# mymote-core.net
KiCad netlist of a schematic drawn in EAGLE
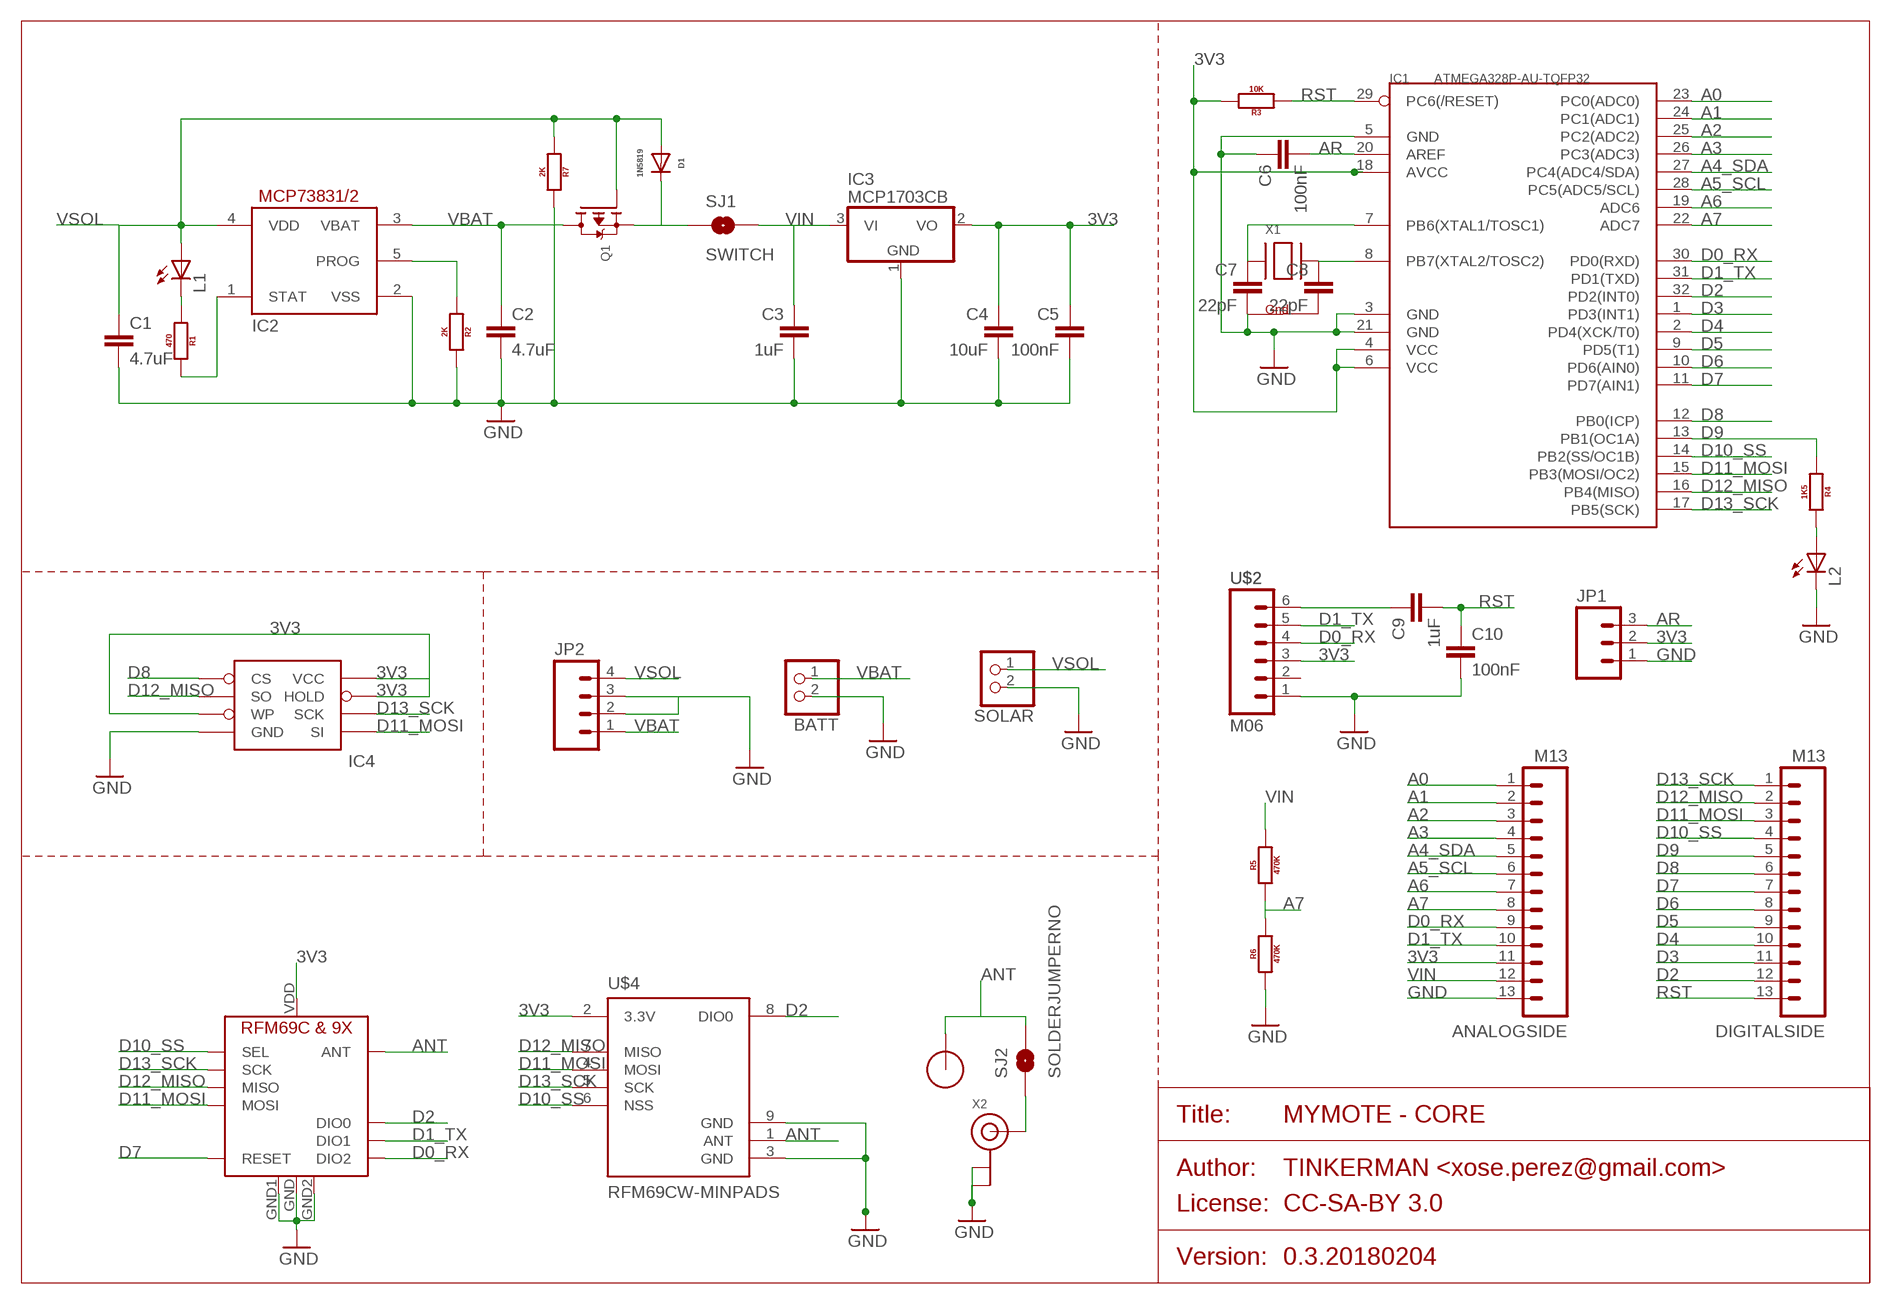
[diagram p0: schematic, sheet 1]

(export (version "E")
  (design (tool "Eeschema 10.0.6"))
  (components
    (comp (ref "ANALOGSIDE")
      (value "M13")
      (footprint "eagle-import:1X13_NO_SILK")
      (libsource (lib "eagle-import") (part "M13"))
    )
    (comp (ref "BATT")
      (value "JST_2PIN-SMT-RA")
      (footprint "eagle-import:JST-PH-2-SMT-RA")
      (libsource (lib "eagle-import") (part "JST_2PIN-SMT-RA"))
    )
    (comp (ref "C1")
      (value "4.7uF")
      (footprint "eagle-import:0805")
      (libsource (lib "eagle-import") (part "C-EU0805"))
    )
    (comp (ref "C2")
      (value "4.7uF")
      (footprint "eagle-import:0805")
      (libsource (lib "eagle-import") (part "C-EU0805"))
    )
    (comp (ref "C3")
      (value "1uF")
      (footprint "eagle-import:0805")
      (libsource (lib "eagle-import") (part "C-EU0805"))
    )
    (comp (ref "C4")
      (value "10uF")
      (footprint "eagle-import:0805")
      (libsource (lib "eagle-import") (part "C-EU0805"))
    )
    (comp (ref "C5")
      (value "100nF")
      (footprint "eagle-import:0805")
      (libsource (lib "eagle-import") (part "C-EU0805"))
    )
    (comp (ref "C6")
      (value "100nF")
      (footprint "eagle-import:0805")
      (libsource (lib "eagle-import") (part "C-EU0805"))
    )
    (comp (ref "C7")
      (value "22pF")
      (footprint "eagle-import:0805")
      (libsource (lib "eagle-import") (part "C-EU0805"))
    )
    (comp (ref "C8")
      (value "22pF")
      (footprint "eagle-import:0805")
      (libsource (lib "eagle-import") (part "C-EU0805"))
    )
    (comp (ref "C9")
      (value "1uF")
      (footprint "eagle-import:0805")
      (libsource (lib "eagle-import") (part "C-EU0805"))
    )
    (comp (ref "C10")
      (value "100nF")
      (footprint "eagle-import:0805")
      (libsource (lib "eagle-import") (part "C-EU0805"))
    )
    (comp (ref "D1")
      (value "1N5819")
      (footprint "eagle-import:0805_DIODE")
      (libsource (lib "eagle-import") (part "DIODE-SMD"))
    )
    (comp (ref "DIGITALSIDE")
      (value "M13")
      (footprint "eagle-import:1X13_NO_SILK")
      (libsource (lib "eagle-import") (part "M13"))
    )
    (comp (ref "IC1")
      (value "ATMEGA328P-AU-TQFP32")
      (footprint "eagle-import:TQFP32-0.8-7X7MM")
      (fields (field (name "MPN") "ATMEGA328P-AU"))
      (libsource (lib "eagle-import") (part "MCU-ATMEGA328P-AU(TQFP32)"))
    )
    (comp (ref "IC2")
      (value "MCP73831/OT")
      (footprint "eagle-import:SOT23-5L")
      (libsource (lib "eagle-import") (part "MCP73831/OT"))
    )
    (comp (ref "IC3")
      (value "MCP1703CB")
      (footprint "eagle-import:SOT23")
      (libsource (lib "eagle-import") (part "MCP1703CB"))
    )
    (comp (ref "IC4")
      (value "AT25F512BWIDE_5.3MM")
      (footprint "eagle-import:SO08WIDE")
      (libsource (lib "eagle-import") (part "AT25F512BWIDE_5.3MM"))
    )
    (comp (ref "JP1")
      (value "M03PTH")
      (footprint "eagle-import:1X03")
      (libsource (lib "eagle-import") (part "M03PTH"))
    )
    (comp (ref "JP2")
      (value "M04PTH")
      (footprint "eagle-import:1X04")
      (libsource (lib "eagle-import") (part "M04PTH"))
    )
    (comp (ref "L1")
      (value "LED_0805")
      (footprint "eagle-import:0805_DIODE")
      (libsource (lib "eagle-import") (part "LED_0805"))
    )
    (comp (ref "L2")
      (value "LED_0805")
      (footprint "eagle-import:0805_DIODE")
      (libsource (lib "eagle-import") (part "LED_0805"))
    )
    (comp (ref "Q1")
      (value "MOSFET-PWIDE")
      (footprint "eagle-import:SOT23-WIDE")
      (libsource (lib "eagle-import") (part "MOSFET-PWIDE"))
    )
    (comp (ref "R1")
      (value "470")
      (footprint "eagle-import:0805")
      (libsource (lib "eagle-import") (part "RESISTOR0805"))
    )
    (comp (ref "R2")
      (value "2K")
      (footprint "eagle-import:0805")
      (libsource (lib "eagle-import") (part "RESISTOR0805"))
    )
    (comp (ref "R3")
      (value "10K")
      (footprint "eagle-import:0805")
      (libsource (lib "eagle-import") (part "RESISTOR0805"))
    )
    (comp (ref "R4")
      (value "1K5")
      (footprint "eagle-import:0805")
      (libsource (lib "eagle-import") (part "RESISTOR0805"))
    )
    (comp (ref "R5")
      (value "470K")
      (footprint "eagle-import:0805")
      (libsource (lib "eagle-import") (part "RESISTOR0805"))
    )
    (comp (ref "R6")
      (value "470K")
      (footprint "eagle-import:0805")
      (libsource (lib "eagle-import") (part "RESISTOR0805"))
    )
    (comp (ref "R7")
      (value "2K")
      (footprint "eagle-import:0805")
      (libsource (lib "eagle-import") (part "RESISTOR0805"))
    )
    (comp (ref "SJ1")
      (value "SWITCH")
      (footprint "eagle-import:SJ_2S-TRACE-PTH")
      (libsource (lib "eagle-import") (part "SOLDERJUMPERTRACE-PTH"))
    )
    (comp (ref "SJ2")
      (value "SOLDERJUMPERNO")
      (footprint "eagle-import:SJ_2S-NO")
      (libsource (lib "eagle-import") (part "SOLDERJUMPERNO"))
    )
    (comp (ref "SOLAR")
      (value "JST_2PIN-SMT-RA")
      (footprint "eagle-import:JST-PH-2-SMT-RA")
      (libsource (lib "eagle-import") (part "JST_2PIN-SMT-RA"))
    )
    (comp (ref "U$1")
      (value "RFM12B_ANTENNA")
      (footprint "eagle-import:RFM12B-ANTENNA")
      (libsource (lib "eagle-import") (part "RFM12B_ANTENNA"))
    )
    (comp (ref "U$2")
      (value "M06")
      (footprint "eagle-import:1X06_NO_SILK")
      (libsource (lib "eagle-import") (part "M06"))
    )
    (comp (ref "U$3")
      (value "RFM69HCW-RFM95")
      (footprint "eagle-import:RFM69HCW-RFM95-MINPADS")
      (libsource (lib "eagle-import") (part "RFM69HCW-RFM95"))
    )
    (comp (ref "U$4")
      (value "RFM69CW-MINPADS")
      (footprint "eagle-import:RFM69CW-MINPADS")
      (libsource (lib "eagle-import") (part "RFM69CW-MINPADS"))
    )
    (comp (ref "X1")
      (value "XTAL-4-3225")
      (footprint "eagle-import:NX3225")
      (libsource (lib "eagle-import") (part "XTAL-4-3225"))
    )
    (comp (ref "X2")
      (value "ANTENNA_U.FL")
      (footprint "eagle-import:U.FL")
      (libsource (lib "eagle-import") (part "ANTENNA_U.FL"))
    )
  )
  (nets
    (net (code "1") (name "/3V3") (class "Default")
      (node (ref "ANALOGSIDE") (pin "11") (pinfunction "11_11") (pintype "passive"))
      (node (ref "C4") (pin "1") (pinfunction "1_1") (pintype "passive"))
      (node (ref "C5") (pin "1") (pinfunction "1_1") (pintype "passive"))
      (node (ref "IC1") (pin "18") (pinfunction "AVCC_18") (pintype "bidirectional"))
      (node (ref "IC1") (pin "4") (pinfunction "VCC_4") (pintype "bidirectional"))
      (node (ref "IC1") (pin "6") (pinfunction "VCC_6") (pintype "bidirectional"))
      (node (ref "IC3") (pin "2") (pinfunction "VO_2") (pintype "passive"))
      (node (ref "IC4") (pin "3") (pinfunction "WP_3") (pintype "bidirectional"))
      (node (ref "IC4") (pin "7") (pinfunction "HOLD_7") (pintype "bidirectional"))
      (node (ref "IC4") (pin "8") (pinfunction "VCC_8") (pintype "bidirectional"))
      (node (ref "JP1") (pin "2") (pinfunction "2_2") (pintype "passive"))
      (node (ref "R3") (pin "2") (pinfunction "2_2") (pintype "passive"))
      (node (ref "U$2") (pin "3") (pinfunction "3_3") (pintype "passive"))
      (node (ref "U$3") (pin "VDD") (pinfunction "VCC_VDD") (pintype "power_in"))
      (node (ref "U$4") (pin "2") (pinfunction "3.3V_2") (pintype "power_in"))
    )
    (net (code "2") (name "/A0") (class "Default")
      (node (ref "ANALOGSIDE") (pin "1") (pinfunction "1_1") (pintype "passive"))
      (node (ref "IC1") (pin "23") (pinfunction "PC0(ADC0)_23") (pintype "bidirectional"))
    )
    (net (code "3") (name "/A1") (class "Default")
      (node (ref "ANALOGSIDE") (pin "2") (pinfunction "2_2") (pintype "passive"))
      (node (ref "IC1") (pin "24") (pinfunction "PC1(ADC1)_24") (pintype "bidirectional"))
    )
    (net (code "4") (name "/A2") (class "Default")
      (node (ref "ANALOGSIDE") (pin "3") (pinfunction "3_3") (pintype "passive"))
      (node (ref "IC1") (pin "25") (pinfunction "PC2(ADC2)_25") (pintype "bidirectional"))
    )
    (net (code "5") (name "/A3") (class "Default")
      (node (ref "ANALOGSIDE") (pin "4") (pinfunction "4_4") (pintype "passive"))
      (node (ref "IC1") (pin "26") (pinfunction "PC3(ADC3)_26") (pintype "bidirectional"))
    )
    (net (code "6") (name "/A4_SDA") (class "Default")
      (node (ref "ANALOGSIDE") (pin "5") (pinfunction "5_5") (pintype "passive"))
      (node (ref "IC1") (pin "27") (pinfunction "PC4(ADC4/SDA)_27") (pintype "bidirectional"))
    )
    (net (code "7") (name "/A5_SCL") (class "Default")
      (node (ref "ANALOGSIDE") (pin "6") (pinfunction "6_6") (pintype "passive"))
      (node (ref "IC1") (pin "28") (pinfunction "PC5(ADC5/SCL)_28") (pintype "bidirectional"))
    )
    (net (code "8") (name "/A6") (class "Default")
      (node (ref "ANALOGSIDE") (pin "7") (pinfunction "7_7") (pintype "passive"))
      (node (ref "IC1") (pin "19") (pinfunction "ADC6_19") (pintype "bidirectional"))
    )
    (net (code "9") (name "/A7") (class "Default")
      (node (ref "ANALOGSIDE") (pin "8") (pinfunction "8_8") (pintype "passive"))
      (node (ref "IC1") (pin "22") (pinfunction "ADC7_22") (pintype "bidirectional"))
      (node (ref "R5") (pin "1") (pinfunction "1_1") (pintype "passive"))
      (node (ref "R6") (pin "2") (pinfunction "2_2") (pintype "passive"))
    )
    (net (code "10") (name "/ANT") (class "Default")
      (node (ref "SJ2") (pin "2") (pinfunction "2_2") (pintype "passive"))
      (node (ref "U$1") (pin "P$1") (pinfunction "1_P$1") (pintype "bidirectional"))
      (node (ref "U$3") (pin "ANT") (pinfunction "ANT_ANT") (pintype "passive"))
      (node (ref "U$4") (pin "1") (pinfunction "ANT_1") (pintype "passive"))
    )
    (net (code "11") (name "/AR") (class "Default")
      (node (ref "C6") (pin "2") (pinfunction "2_2") (pintype "passive"))
      (node (ref "IC1") (pin "20") (pinfunction "AREF_20") (pintype "bidirectional"))
      (node (ref "JP1") (pin "3") (pinfunction "3_3") (pintype "passive"))
    )
    (net (code "12") (name "/D0_RX") (class "Default")
      (node (ref "ANALOGSIDE") (pin "9") (pinfunction "9_9") (pintype "passive"))
      (node (ref "IC1") (pin "30") (pinfunction "PD0(RXD)_30") (pintype "bidirectional"))
      (node (ref "U$2") (pin "4") (pinfunction "4_4") (pintype "passive"))
      (node (ref "U$3") (pin "DIO2") (pinfunction "DIO2_DIO2") (pintype "bidirectional"))
    )
    (net (code "13") (name "/D1_TX") (class "Default")
      (node (ref "ANALOGSIDE") (pin "10") (pinfunction "10_10") (pintype "passive"))
      (node (ref "IC1") (pin "31") (pinfunction "PD1(TXD)_31") (pintype "bidirectional"))
      (node (ref "U$2") (pin "5") (pinfunction "5_5") (pintype "passive"))
      (node (ref "U$3") (pin "DIO1") (pinfunction "DIO1_DIO1") (pintype "bidirectional"))
    )
    (net (code "14") (name "/D2") (class "Default")
      (node (ref "DIGITALSIDE") (pin "12") (pinfunction "12_12") (pintype "passive"))
      (node (ref "IC1") (pin "32") (pinfunction "PD2(INT0)_32") (pintype "bidirectional"))
      (node (ref "U$3") (pin "DIO0") (pinfunction "DIO0_DIO0") (pintype "bidirectional"))
      (node (ref "U$4") (pin "8") (pinfunction "DIO0_8") (pintype "bidirectional"))
    )
    (net (code "15") (name "/D3") (class "Default")
      (node (ref "DIGITALSIDE") (pin "11") (pinfunction "11_11") (pintype "passive"))
      (node (ref "IC1") (pin "1") (pinfunction "PD3(INT1)_1") (pintype "bidirectional"))
    )
    (net (code "16") (name "/D4") (class "Default")
      (node (ref "DIGITALSIDE") (pin "10") (pinfunction "10_10") (pintype "passive"))
      (node (ref "IC1") (pin "2") (pinfunction "PD4(XCK/T0)_2") (pintype "bidirectional"))
    )
    (net (code "17") (name "/D5") (class "Default")
      (node (ref "DIGITALSIDE") (pin "9") (pinfunction "9_9") (pintype "passive"))
      (node (ref "IC1") (pin "9") (pinfunction "PD5(T1)_9") (pintype "bidirectional"))
    )
    (net (code "18") (name "/D6") (class "Default")
      (node (ref "DIGITALSIDE") (pin "8") (pinfunction "8_8") (pintype "passive"))
      (node (ref "IC1") (pin "10") (pinfunction "PD6(AIN0)_10") (pintype "bidirectional"))
    )
    (net (code "19") (name "/D7") (class "Default")
      (node (ref "DIGITALSIDE") (pin "7") (pinfunction "7_7") (pintype "passive"))
      (node (ref "IC1") (pin "11") (pinfunction "PD7(AIN1)_11") (pintype "bidirectional"))
      (node (ref "U$3") (pin "RESET") (pinfunction "RESET_RESET") (pintype "input"))
    )
    (net (code "20") (name "/D8") (class "Default")
      (node (ref "DIGITALSIDE") (pin "6") (pinfunction "6_6") (pintype "passive"))
      (node (ref "IC1") (pin "12") (pinfunction "PB0(ICP)_12") (pintype "bidirectional"))
      (node (ref "IC4") (pin "1") (pinfunction "CS_1") (pintype "bidirectional"))
    )
    (net (code "21") (name "/D9") (class "Default")
      (node (ref "DIGITALSIDE") (pin "5") (pinfunction "5_5") (pintype "passive"))
      (node (ref "IC1") (pin "13") (pinfunction "PB1(OC1A)_13") (pintype "bidirectional"))
      (node (ref "R4") (pin "1") (pinfunction "1_1") (pintype "passive"))
    )
    (net (code "22") (name "/D10_SS") (class "Default")
      (node (ref "DIGITALSIDE") (pin "4") (pinfunction "4_4") (pintype "passive"))
      (node (ref "IC1") (pin "14") (pinfunction "PB2(SS/OC1B)_14") (pintype "bidirectional"))
      (node (ref "U$3") (pin "NSS") (pinfunction "SEL_NSS") (pintype "input"))
      (node (ref "U$4") (pin "6") (pinfunction "NSS_6") (pintype "input"))
    )
    (net (code "23") (name "/D11_MOSI") (class "Default")
      (node (ref "DIGITALSIDE") (pin "3") (pinfunction "3_3") (pintype "passive"))
      (node (ref "IC1") (pin "15") (pinfunction "PB3(MOSI/OC2)_15") (pintype "bidirectional"))
      (node (ref "IC4") (pin "5") (pinfunction "SI_5") (pintype "bidirectional"))
      (node (ref "U$3") (pin "MOSI") (pinfunction "MOSI_MOSI") (pintype "input"))
      (node (ref "U$4") (pin "4") (pinfunction "MOSI_4") (pintype "input"))
    )
    (net (code "24") (name "/D12_MISO") (class "Default")
      (node (ref "DIGITALSIDE") (pin "2") (pinfunction "2_2") (pintype "passive"))
      (node (ref "IC1") (pin "16") (pinfunction "PB4(MISO)_16") (pintype "bidirectional"))
      (node (ref "IC4") (pin "2") (pinfunction "SO_2") (pintype "bidirectional"))
      (node (ref "U$3") (pin "MISO") (pinfunction "MISO_MISO") (pintype "output"))
      (node (ref "U$4") (pin "7") (pinfunction "MISO_7") (pintype "bidirectional"))
    )
    (net (code "25") (name "/D13_SCK") (class "Default")
      (node (ref "DIGITALSIDE") (pin "1") (pinfunction "1_1") (pintype "passive"))
      (node (ref "IC1") (pin "17") (pinfunction "PB5(SCK)_17") (pintype "bidirectional"))
      (node (ref "IC4") (pin "6") (pinfunction "SCK_6") (pintype "bidirectional"))
      (node (ref "U$3") (pin "SCK") (pinfunction "SCK_SCK") (pintype "input"))
      (node (ref "U$4") (pin "5") (pinfunction "SCK_5") (pintype "input"))
    )
    (net (code "26") (name "/RST") (class "Default")
      (node (ref "C10") (pin "1") (pinfunction "1_1") (pintype "passive"))
      (node (ref "C9") (pin "2") (pinfunction "2_2") (pintype "passive"))
      (node (ref "DIGITALSIDE") (pin "13") (pinfunction "13_13") (pintype "passive"))
      (node (ref "IC1") (pin "29") (pinfunction "PC6(/RESET)_29") (pintype "bidirectional"))
      (node (ref "R3") (pin "1") (pinfunction "1_1") (pintype "passive"))
    )
    (net (code "27") (name "/VBAT") (class "Default")
      (node (ref "BATT") (pin "1") (pinfunction "2_1") (pintype "passive"))
      (node (ref "C2") (pin "1") (pinfunction "1_1") (pintype "passive"))
      (node (ref "IC2") (pin "3") (pinfunction "VBAT_3") (pintype "bidirectional"))
      (node (ref "JP2") (pin "1") (pinfunction "1_1") (pintype "passive"))
      (node (ref "Q1") (pin "3") (pinfunction "D_3") (pintype "passive"))
    )
    (net (code "28") (name "/VIN") (class "Default")
      (node (ref "ANALOGSIDE") (pin "12") (pinfunction "12_12") (pintype "passive"))
      (node (ref "C3") (pin "1") (pinfunction "1_1") (pintype "passive"))
      (node (ref "IC3") (pin "3") (pinfunction "VI_3") (pintype "input"))
      (node (ref "R5") (pin "2") (pinfunction "2_2") (pintype "passive"))
      (node (ref "SJ1") (pin "2") (pinfunction "2_2") (pintype "passive"))
    )
    (net (code "29") (name "/VSOL") (class "Default")
      (node (ref "C1") (pin "1") (pinfunction "1_1") (pintype "passive"))
      (node (ref "D1") (pin "A") (pinfunction "A_A") (pintype "passive"))
      (node (ref "IC2") (pin "4") (pinfunction "VDD_4") (pintype "power_in"))
      (node (ref "JP2") (pin "4") (pinfunction "4_4") (pintype "passive"))
      (node (ref "L1") (pin "A") (pinfunction "A_A") (pintype "passive"))
      (node (ref "Q1") (pin "1") (pinfunction "G_1") (pintype "passive"))
      (node (ref "R7") (pin "1") (pinfunction "1_1") (pintype "passive"))
      (node (ref "SOLAR") (pin "1") (pinfunction "2_1") (pintype "passive"))
    )
    (net (code "30") (name "GND") (class "Default")
      (node (ref "ANALOGSIDE") (pin "13") (pinfunction "13_13") (pintype "passive"))
      (node (ref "BATT") (pin "2") (pinfunction "1_2") (pintype "passive"))
      (node (ref "C1") (pin "2") (pinfunction "2_2") (pintype "passive"))
      (node (ref "C10") (pin "2") (pinfunction "2_2") (pintype "passive"))
      (node (ref "C2") (pin "2") (pinfunction "2_2") (pintype "passive"))
      (node (ref "C3") (pin "2") (pinfunction "2_2") (pintype "passive"))
      (node (ref "C4") (pin "2") (pinfunction "2_2") (pintype "passive"))
      (node (ref "C5") (pin "2") (pinfunction "2_2") (pintype "passive"))
      (node (ref "C6") (pin "1") (pinfunction "1_1") (pintype "passive"))
      (node (ref "C7") (pin "2") (pinfunction "2_2") (pintype "passive"))
      (node (ref "IC1") (pin "21") (pinfunction "GND_21") (pintype "bidirectional"))
      (node (ref "IC1") (pin "3") (pinfunction "GND_3") (pintype "bidirectional"))
      (node (ref "IC1") (pin "5") (pinfunction "GND_5") (pintype "bidirectional"))
      (node (ref "IC2") (pin "2") (pinfunction "VSS_2") (pintype "power_in"))
      (node (ref "IC3") (pin "1") (pinfunction "GND_1") (pintype "passive"))
      (node (ref "IC4") (pin "4") (pinfunction "GND_4") (pintype "bidirectional"))
      (node (ref "JP1") (pin "1") (pinfunction "1_1") (pintype "passive"))
      (node (ref "JP2") (pin "2") (pinfunction "2_2") (pintype "passive"))
      (node (ref "JP2") (pin "3") (pinfunction "3_3") (pintype "passive"))
      (node (ref "L2") (pin "C") (pinfunction "C_C") (pintype "passive"))
      (node (ref "R2") (pin "2") (pinfunction "2_2") (pintype "passive"))
      (node (ref "R6") (pin "1") (pinfunction "1_1") (pintype "passive"))
      (node (ref "R7") (pin "2") (pinfunction "2_2") (pintype "passive"))
      (node (ref "SOLAR") (pin "2") (pinfunction "1_2") (pintype "passive"))
      (node (ref "U$2") (pin "1") (pinfunction "1_1") (pintype "passive"))
      (node (ref "U$3") (pin "GND") (pinfunction "GND_GND") (pintype "power_in"))
      (node (ref "U$3") (pin "GND1") (pinfunction "GND1_GND1") (pintype "power_in"))
      (node (ref "U$3") (pin "GND2") (pinfunction "GND2_GND2") (pintype "power_in"))
      (node (ref "U$4") (pin "3") (pinfunction "GND_3") (pintype "power_in"))
      (node (ref "U$4") (pin "9") (pinfunction "GND_9") (pintype "power_in"))
      (node (ref "X1") (pin "4") (pinfunction "G1_4") (pintype "power_in"))
      (node (ref "X2") (pin "1") (pinfunction "GND_1") (pintype "passive"))
      (node (ref "X2") (pin "2") (pinfunction "GND_2") (pintype "passive"))
    )
    (net (code "31") (name "Net-(C9-Pad1)") (class "Default")
      (node (ref "C9") (pin "1") (pinfunction "1_1") (pintype "passive"))
      (node (ref "U$2") (pin "6") (pinfunction "6_6") (pintype "passive"))
    )
    (net (code "32") (name "Net-(IC1-PB6(XTAL1{slash}TOSC1))") (class "Default")
      (node (ref "C7") (pin "1") (pinfunction "1_1") (pintype "passive"))
      (node (ref "IC1") (pin "7") (pinfunction "PB6(XTAL1/TOSC1)_7") (pintype "bidirectional"))
      (node (ref "X1") (pin "1") (pinfunction "X1_1") (pintype "bidirectional"))
    )
    (net (code "33") (name "Net-(IC1-PB7(XTAL2{slash}TOSC2))") (class "Default")
      (node (ref "C8") (pin "1") (pinfunction "1_1") (pintype "passive"))
      (node (ref "IC1") (pin "8") (pinfunction "PB7(XTAL2/TOSC2)_8") (pintype "bidirectional"))
      (node (ref "X1") (pin "3") (pinfunction "X2_3") (pintype "bidirectional"))
    )
    (net (code "34") (name "Net-(IC2-PROG)") (class "Default")
      (node (ref "IC2") (pin "5") (pinfunction "PROG_5") (pintype "input"))
      (node (ref "R2") (pin "1") (pinfunction "1_1") (pintype "passive"))
    )
    (net (code "35") (name "Net-(IC2-STAT)") (class "Default")
      (node (ref "IC2") (pin "1") (pinfunction "STAT_1") (pintype "output"))
      (node (ref "R1") (pin "2") (pinfunction "2_2") (pintype "passive"))
    )
    (net (code "36") (name "Net-(L1-PadC)") (class "Default")
      (node (ref "L1") (pin "C") (pinfunction "C_C") (pintype "passive"))
      (node (ref "R1") (pin "1") (pinfunction "1_1") (pintype "passive"))
    )
    (net (code "37") (name "Net-(L2-PadA)") (class "Default")
      (node (ref "L2") (pin "A") (pinfunction "A_A") (pintype "passive"))
      (node (ref "R4") (pin "2") (pinfunction "2_2") (pintype "passive"))
    )
    (net (code "38") (name "Net-(Q1-S)") (class "Default")
      (node (ref "D1") (pin "C") (pinfunction "C_C") (pintype "passive"))
      (node (ref "Q1") (pin "2") (pinfunction "S_2") (pintype "passive"))
      (node (ref "SJ1") (pin "1") (pinfunction "1_1") (pintype "passive"))
    )
    (net (code "39") (name "Net-(X1-G2)") (class "Default")
      (node (ref "C8") (pin "2") (pinfunction "2_2") (pintype "passive"))
      (node (ref "X1") (pin "2") (pinfunction "G2_2") (pintype "power_in"))
    )
    (net (code "40") (name "Net-(X2-SIGNAL)") (class "Default")
      (node (ref "SJ2") (pin "1") (pinfunction "1_1") (pintype "passive"))
      (node (ref "X2") (pin "3") (pinfunction "SIGNAL_3") (pintype "passive"))
    )
    (net (code "41") (name "unconnected-(U$2-Pad2)") (class "Default")
      (node (ref "U$2") (pin "2") (pinfunction "2_2") (pintype "passive"))
    )
  )
)
